# btl.net
KiCad netlist of a schematic drawn in Altium Designer
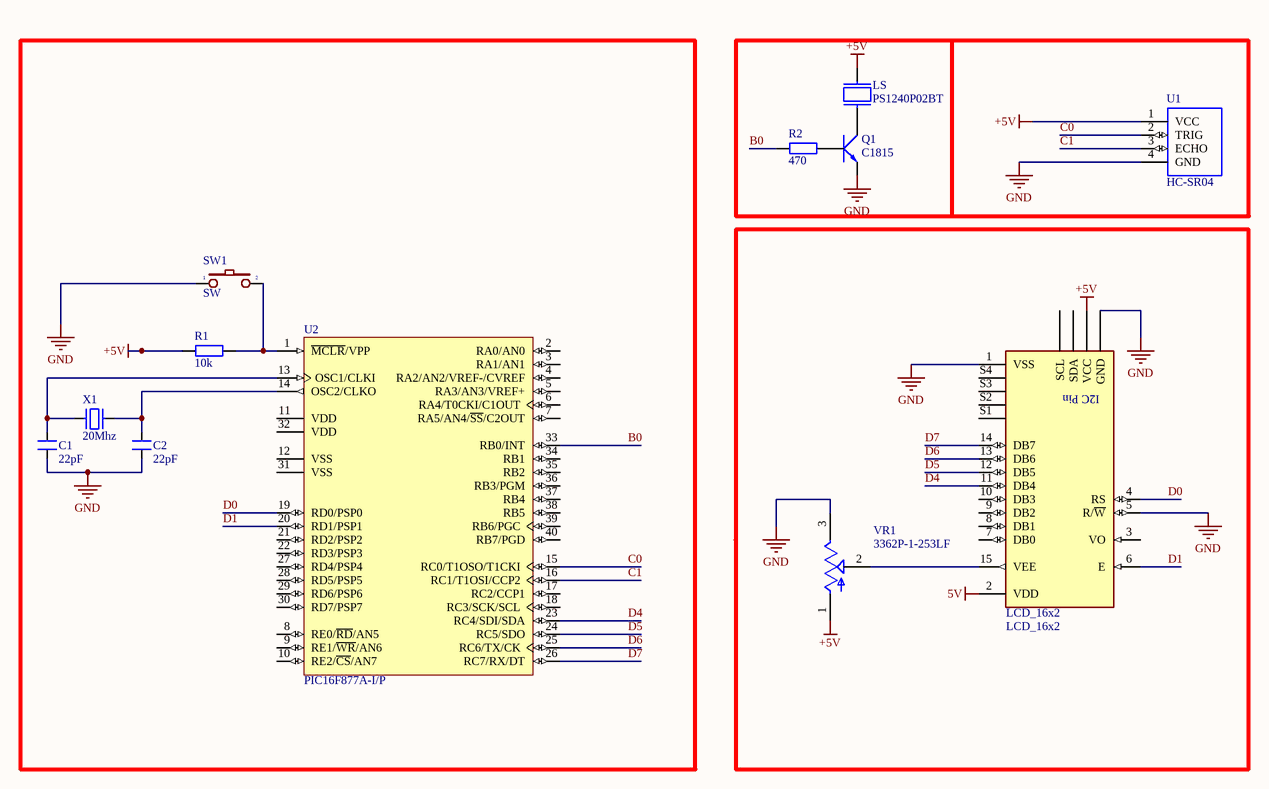
[diagram p0: btl.SchDoc]

(export (version "E")
  (design (tool "Eeschema 10.0.6"))
  (components
    (comp (ref "C1")
      (value "22pF")
      (footprint "CN2")
      (description "Cap np 104 => 105pF")
      (libsource (lib "syhaunguyen") (part "CN2"))
    )
    (comp (ref "C2")
      (value "22pF")
      (footprint "CN2")
      (description "Cap np 104 => 105pF")
      (libsource (lib "syhaunguyen") (part "CN2"))
    )
    (comp (ref "LCD_16x2")
      (value "LCD_16x2")
      (footprint "LCD_16x2")
      (description "Display: LCD; alphanumeric; STN Negative; 16x2; blue; LED; PIN: 16")
      (fields (field (name "MP") "RC1602B-BIW-CSV"))
      (libsource (lib "LCD_16x2") (part "LCD_16x2"))
    )
    (comp (ref "LS")
      (value "PS1240P02BT")
      (footprint "XDCR_PS1240P02BT")
      (description "Buzzers Transducer, Externally Driven Piezo 3V 4kHz 60dB @ 3V, 10cm Through Hole PC Pins")
      (fields (field (name "MF") "TDK"))
      (libsource (lib "buzzer") (part "PS1240P02BT"))
    )
    (comp (ref "Q1")
      (value "C1815")
      (footprint "QTO-92")
      (description "NPN 600mW, ECB")
      (libsource (lib "syhaunguyen") (part "C1815"))
    )
    (comp (ref "R1")
      (value "10k")
      (footprint "R1/4W")
      (description "Resistor 1/4W")
      (libsource (lib "syhaunguyen") (part "R1/4W"))
    )
    (comp (ref "R2")
      (value "470")
      (footprint "R1/4W")
      (description "Resistor 1/4W")
      (libsource (lib "syhaunguyen") (part "R1/4W"))
    )
    (comp (ref "SW1")
      (value "SW")
      (footprint "SW2")
      (description "Switch button 2 pin")
      (libsource (lib "syhaunguyen") (part "SW2"))
    )
    (comp (ref "U1")
      (value "HC-SR04")
      (footprint "XCVR_HC-SR04")
      (description "Ultrasonic Sensor Module")
      (libsource (lib "HC-SR04") (part "HC-SR04"))
    )
    (comp (ref "U2")
      (value "PIC16F877A-I/P")
      (footprint "PDIP600-P40")
      (fields (field (name "PUBLISHER") "Altium Limited"))
      (libsource (lib "Microchip Microcontroller 8-Bit PIC16") (part "PIC16F877A-I/P"))
    )
    (comp (ref "VR1")
      (value "3362P-1-253LF")
      (footprint "TRIM_3362P-1-253LF")
      (description "25 kOhms 0.5W, 1/2W PC Pins Through Hole Trimmer Potentiometer Cermet 1.0 Turn Top Adjustment")
      (fields (field (name "MF") "Bourns"))
      (libsource (lib "POT_HG") (part "3362P-1-253LF"))
    )
    (comp (ref "X1")
      (value "20Mhz")
      (footprint "XT2")
      (description "Crystal For all Crystal 2pin.")
      (libsource (lib "syhaunguyen") (part "XT2"))
    )
  )
  (nets
    (net (code "1") (name "+5V") (class "Default")
      (node (ref "LCD_16x2") (pin "VCC") (pinfunction "VCC_VCC") (pintype "passive"))
      (node (ref "LS") (pin "2") (pinfunction "2_2") (pintype "passive"))
      (node (ref "R1") (pin "1") (pinfunction "1_1") (pintype "passive"))
      (node (ref "U1") (pin "1") (pinfunction "VCC_1") (pintype "power_in"))
      (node (ref "VR1") (pin "1") (pinfunction "CCW_1") (pintype "passive"))
    )
    (net (code "2") (name "/B0") (class "Default")
      (node (ref "R2") (pin "1") (pinfunction "1_1") (pintype "passive"))
      (node (ref "U2") (pin "33") (pinfunction "RB0/INT_33") (pintype "bidirectional"))
    )
    (net (code "3") (name "/C0") (class "Default")
      (node (ref "U1") (pin "2") (pinfunction "TRIG_2") (pintype "bidirectional"))
      (node (ref "U2") (pin "15") (pinfunction "RC0/T1OSO/T1CKI_15") (pintype "bidirectional"))
    )
    (net (code "4") (name "/C1") (class "Default")
      (node (ref "U1") (pin "3") (pinfunction "ECHO_3") (pintype "bidirectional"))
      (node (ref "U2") (pin "16") (pinfunction "RC1/T1OSI/CCP2_16") (pintype "bidirectional"))
    )
    (net (code "5") (name "/D0") (class "Default")
      (node (ref "LCD_16x2") (pin "4") (pinfunction "RS_4") (pintype "bidirectional"))
      (node (ref "U2") (pin "19") (pinfunction "RD0/PSP0_19") (pintype "bidirectional"))
    )
    (net (code "6") (name "/D1") (class "Default")
      (node (ref "LCD_16x2") (pin "6") (pinfunction "E_6") (pintype "input"))
      (node (ref "U2") (pin "20") (pinfunction "RD1/PSP1_20") (pintype "bidirectional"))
    )
    (net (code "7") (name "/D4") (class "Default")
      (node (ref "LCD_16x2") (pin "11") (pinfunction "DB4_11") (pintype "bidirectional"))
      (node (ref "U2") (pin "23") (pinfunction "RC4/SDI/SDA_23") (pintype "bidirectional"))
    )
    (net (code "8") (name "/D5") (class "Default")
      (node (ref "LCD_16x2") (pin "12") (pinfunction "DB5_12") (pintype "bidirectional"))
      (node (ref "U2") (pin "24") (pinfunction "RC5/SDO_24") (pintype "bidirectional"))
    )
    (net (code "9") (name "/D6") (class "Default")
      (node (ref "LCD_16x2") (pin "13") (pinfunction "DB6_13") (pintype "bidirectional"))
      (node (ref "U2") (pin "25") (pinfunction "RC6/TX/CK_25") (pintype "bidirectional"))
    )
    (net (code "10") (name "/D7") (class "Default")
      (node (ref "LCD_16x2") (pin "14") (pinfunction "DB7_14") (pintype "bidirectional"))
      (node (ref "U2") (pin "26") (pinfunction "RC7/RX/DT_26") (pintype "bidirectional"))
    )
    (net (code "11") (name "5V") (class "Default")
      (node (ref "LCD_16x2") (pin "2") (pinfunction "VDD_2") (pintype "power_in"))
    )
    (net (code "12") (name "GND") (class "Default")
      (node (ref "C1") (pin "1") (pinfunction "1_1") (pintype "passive"))
      (node (ref "C2") (pin "1") (pinfunction "1_1") (pintype "passive"))
      (node (ref "LCD_16x2") (pin "1") (pinfunction "VSS_1") (pintype "power_in"))
      (node (ref "LCD_16x2") (pin "5") (pinfunction "R/~{W}_5") (pintype "bidirectional"))
      (node (ref "LCD_16x2") (pin "GND") (pinfunction "GND_GND") (pintype "passive"))
      (node (ref "Q1") (pin "1") (pinfunction "E_1") (pintype "passive"))
      (node (ref "SW1") (pin "1") (pinfunction "1_1") (pintype "passive"))
      (node (ref "U1") (pin "4") (pinfunction "GND_4") (pintype "power_in"))
      (node (ref "VR1") (pin "3") (pinfunction "CW_3") (pintype "passive"))
    )
    (net (code "13") (name "Net-(LCD_16x2-VEE)") (class "Default")
      (node (ref "LCD_16x2") (pin "15") (pinfunction "VEE_15") (pintype "output"))
      (node (ref "VR1") (pin "2") (pinfunction "WIPER_2") (pintype "passive"))
    )
    (net (code "14") (name "Net-(Q1-B)") (class "Default")
      (node (ref "Q1") (pin "3") (pinfunction "B_3") (pintype "passive"))
      (node (ref "R2") (pin "2") (pinfunction "2_2") (pintype "passive"))
    )
    (net (code "15") (name "Net-(Q1-C)") (class "Default")
      (node (ref "LS") (pin "1") (pinfunction "1_1") (pintype "passive"))
      (node (ref "Q1") (pin "2") (pinfunction "C_2") (pintype "passive"))
    )
    (net (code "16") (name "Net-(U2-OSC1{slash}CLKI)") (class "Default")
      (node (ref "C1") (pin "2") (pinfunction "2_2") (pintype "passive"))
      (node (ref "U2") (pin "13") (pinfunction "OSC1/CLKI_13") (pintype "input"))
      (node (ref "X1") (pin "1") (pinfunction "1_1") (pintype "passive"))
    )
    (net (code "17") (name "Net-(U2-OSC2{slash}CLKO)") (class "Default")
      (node (ref "C2") (pin "2") (pinfunction "2_2") (pintype "passive"))
      (node (ref "U2") (pin "14") (pinfunction "OSC2/CLKO_14") (pintype "output"))
      (node (ref "X1") (pin "2") (pinfunction "2_2") (pintype "passive"))
    )
    (net (code "18") (name "Net-(U2-~{MCLR}{slash}VPP)") (class "Default")
      (node (ref "R1") (pin "2") (pinfunction "2_2") (pintype "passive"))
      (node (ref "SW1") (pin "2") (pinfunction "2_2") (pintype "passive"))
      (node (ref "U2") (pin "1") (pinfunction "~{MCLR}/VPP_1") (pintype "input"))
    )
    (net (code "19") (name "unconnected-(LCD_16x2-DB0-Pad7)") (class "Default")
      (node (ref "LCD_16x2") (pin "7") (pinfunction "DB0_7") (pintype "bidirectional"))
    )
    (net (code "20") (name "unconnected-(LCD_16x2-DB1-Pad8)") (class "Default")
      (node (ref "LCD_16x2") (pin "8") (pinfunction "DB1_8") (pintype "bidirectional"))
    )
    (net (code "21") (name "unconnected-(LCD_16x2-DB2-Pad9)") (class "Default")
      (node (ref "LCD_16x2") (pin "9") (pinfunction "DB2_9") (pintype "bidirectional"))
    )
    (net (code "22") (name "unconnected-(LCD_16x2-DB3-Pad10)") (class "Default")
      (node (ref "LCD_16x2") (pin "10") (pinfunction "DB3_10") (pintype "bidirectional"))
    )
    (net (code "23") (name "unconnected-(LCD_16x2-PadSCL)") (class "Default")
      (node (ref "LCD_16x2") (pin "SCL") (pinfunction "SCL_SCL") (pintype "passive"))
    )
    (net (code "24") (name "unconnected-(LCD_16x2-PadSDA)") (class "Default")
      (node (ref "LCD_16x2") (pin "SDA") (pinfunction "SDA_SDA") (pintype "passive"))
    )
    (net (code "25") (name "unconnected-(LCD_16x2-SHIELD-PadS1)") (class "Default")
      (node (ref "LCD_16x2") (pin "S1") (pinfunction "SHIELD_S1") (pintype "passive"))
    )
    (net (code "26") (name "unconnected-(LCD_16x2-SHIELD-PadS2)") (class "Default")
      (node (ref "LCD_16x2") (pin "S2") (pinfunction "SHIELD_S2") (pintype "passive"))
    )
    (net (code "27") (name "unconnected-(LCD_16x2-SHIELD-PadS3)") (class "Default")
      (node (ref "LCD_16x2") (pin "S3") (pinfunction "SHIELD_S3") (pintype "passive"))
    )
    (net (code "28") (name "unconnected-(LCD_16x2-SHIELD-PadS4)") (class "Default")
      (node (ref "LCD_16x2") (pin "S4") (pinfunction "SHIELD_S4") (pintype "passive"))
    )
    (net (code "29") (name "unconnected-(LCD_16x2-VO-Pad3)") (class "Default")
      (node (ref "LCD_16x2") (pin "3") (pinfunction "VO_3") (pintype "input"))
    )
    (net (code "30") (name "unconnected-(U2-RA0{slash}AN0-Pad2)") (class "Default")
      (node (ref "U2") (pin "2") (pinfunction "RA0/AN0_2") (pintype "bidirectional"))
    )
    (net (code "31") (name "unconnected-(U2-RA1{slash}AN1-Pad3)") (class "Default")
      (node (ref "U2") (pin "3") (pinfunction "RA1/AN1_3") (pintype "bidirectional"))
    )
    (net (code "32") (name "unconnected-(U2-RA2{slash}AN2{slash}VREF-{slash}CVREF-Pad4)") (class "Default")
      (node (ref "U2") (pin "4") (pinfunction "RA2/AN2/VREF-/CVREF_4") (pintype "bidirectional"))
    )
    (net (code "33") (name "unconnected-(U2-RA3{slash}AN3{slash}VREF+-Pad5)") (class "Default")
      (node (ref "U2") (pin "5") (pinfunction "RA3/AN3/VREF+_5") (pintype "bidirectional"))
    )
    (net (code "34") (name "unconnected-(U2-RA4{slash}T0CKI{slash}C1OUT-Pad6)") (class "Default")
      (node (ref "U2") (pin "6") (pinfunction "RA4/T0CKI/C1OUT_6") (pintype "bidirectional"))
    )
    (net (code "35") (name "unconnected-(U2-RA5{slash}AN4{slash}~{SS}{slash}C2OUT-Pad7)") (class "Default")
      (node (ref "U2") (pin "7") (pinfunction "RA5/AN4/~{SS}/C2OUT_7") (pintype "bidirectional"))
    )
    (net (code "36") (name "unconnected-(U2-RB1-Pad34)") (class "Default")
      (node (ref "U2") (pin "34") (pinfunction "RB1_34") (pintype "bidirectional"))
    )
    (net (code "37") (name "unconnected-(U2-RB2-Pad35)") (class "Default")
      (node (ref "U2") (pin "35") (pinfunction "RB2_35") (pintype "bidirectional"))
    )
    (net (code "38") (name "unconnected-(U2-RB3{slash}PGM-Pad36)") (class "Default")
      (node (ref "U2") (pin "36") (pinfunction "RB3/PGM_36") (pintype "bidirectional"))
    )
    (net (code "39") (name "unconnected-(U2-RB4-Pad37)") (class "Default")
      (node (ref "U2") (pin "37") (pinfunction "RB4_37") (pintype "bidirectional"))
    )
    (net (code "40") (name "unconnected-(U2-RB5-Pad38)") (class "Default")
      (node (ref "U2") (pin "38") (pinfunction "RB5_38") (pintype "bidirectional"))
    )
    (net (code "41") (name "unconnected-(U2-RB6{slash}PGC-Pad39)") (class "Default")
      (node (ref "U2") (pin "39") (pinfunction "RB6/PGC_39") (pintype "bidirectional"))
    )
    (net (code "42") (name "unconnected-(U2-RB7{slash}PGD-Pad40)") (class "Default")
      (node (ref "U2") (pin "40") (pinfunction "RB7/PGD_40") (pintype "bidirectional"))
    )
    (net (code "43") (name "unconnected-(U2-RC2{slash}CCP1-Pad17)") (class "Default")
      (node (ref "U2") (pin "17") (pinfunction "RC2/CCP1_17") (pintype "bidirectional"))
    )
    (net (code "44") (name "unconnected-(U2-RC3{slash}SCK{slash}SCL-Pad18)") (class "Default")
      (node (ref "U2") (pin "18") (pinfunction "RC3/SCK/SCL_18") (pintype "bidirectional"))
    )
    (net (code "45") (name "unconnected-(U2-RD2{slash}PSP2-Pad21)") (class "Default")
      (node (ref "U2") (pin "21") (pinfunction "RD2/PSP2_21") (pintype "bidirectional"))
    )
    (net (code "46") (name "unconnected-(U2-RD3{slash}PSP3-Pad22)") (class "Default")
      (node (ref "U2") (pin "22") (pinfunction "RD3/PSP3_22") (pintype "bidirectional"))
    )
    (net (code "47") (name "unconnected-(U2-RD4{slash}PSP4-Pad27)") (class "Default")
      (node (ref "U2") (pin "27") (pinfunction "RD4/PSP4_27") (pintype "bidirectional"))
    )
    (net (code "48") (name "unconnected-(U2-RD5{slash}PSP5-Pad28)") (class "Default")
      (node (ref "U2") (pin "28") (pinfunction "RD5/PSP5_28") (pintype "bidirectional"))
    )
    (net (code "49") (name "unconnected-(U2-RD6{slash}PSP6-Pad29)") (class "Default")
      (node (ref "U2") (pin "29") (pinfunction "RD6/PSP6_29") (pintype "bidirectional"))
    )
    (net (code "50") (name "unconnected-(U2-RD7{slash}PSP7-Pad30)") (class "Default")
      (node (ref "U2") (pin "30") (pinfunction "RD7/PSP7_30") (pintype "bidirectional"))
    )
    (net (code "51") (name "unconnected-(U2-RE0{slash}~{RD}{slash}AN5-Pad8)") (class "Default")
      (node (ref "U2") (pin "8") (pinfunction "RE0/~{RD}/AN5_8") (pintype "bidirectional"))
    )
    (net (code "52") (name "unconnected-(U2-RE1{slash}~{WR}{slash}AN6-Pad9)") (class "Default")
      (node (ref "U2") (pin "9") (pinfunction "RE1/~{WR}/AN6_9") (pintype "bidirectional"))
    )
    (net (code "53") (name "unconnected-(U2-RE2{slash}~{CS}{slash}AN7-Pad10)") (class "Default")
      (node (ref "U2") (pin "10") (pinfunction "RE2/~{CS}/AN7_10") (pintype "bidirectional"))
    )
    (net (code "54") (name "unconnected-(U2-VDD-Pad11)") (class "Default")
      (node (ref "U2") (pin "11") (pinfunction "VDD_11") (pintype "power_in"))
    )
    (net (code "55") (name "unconnected-(U2-VDD-Pad32)") (class "Default")
      (node (ref "U2") (pin "32") (pinfunction "VDD_32") (pintype "power_in"))
    )
    (net (code "56") (name "unconnected-(U2-VSS-Pad12)") (class "Default")
      (node (ref "U2") (pin "12") (pinfunction "VSS_12") (pintype "power_in"))
    )
    (net (code "57") (name "unconnected-(U2-VSS-Pad31)") (class "Default")
      (node (ref "U2") (pin "31") (pinfunction "VSS_31") (pintype "power_in"))
    )
  )
)
